# ProProject_Access_Control_USB_Hub_Switch.net
KiCad netlist of a schematic drawn in EasyEDA Pro
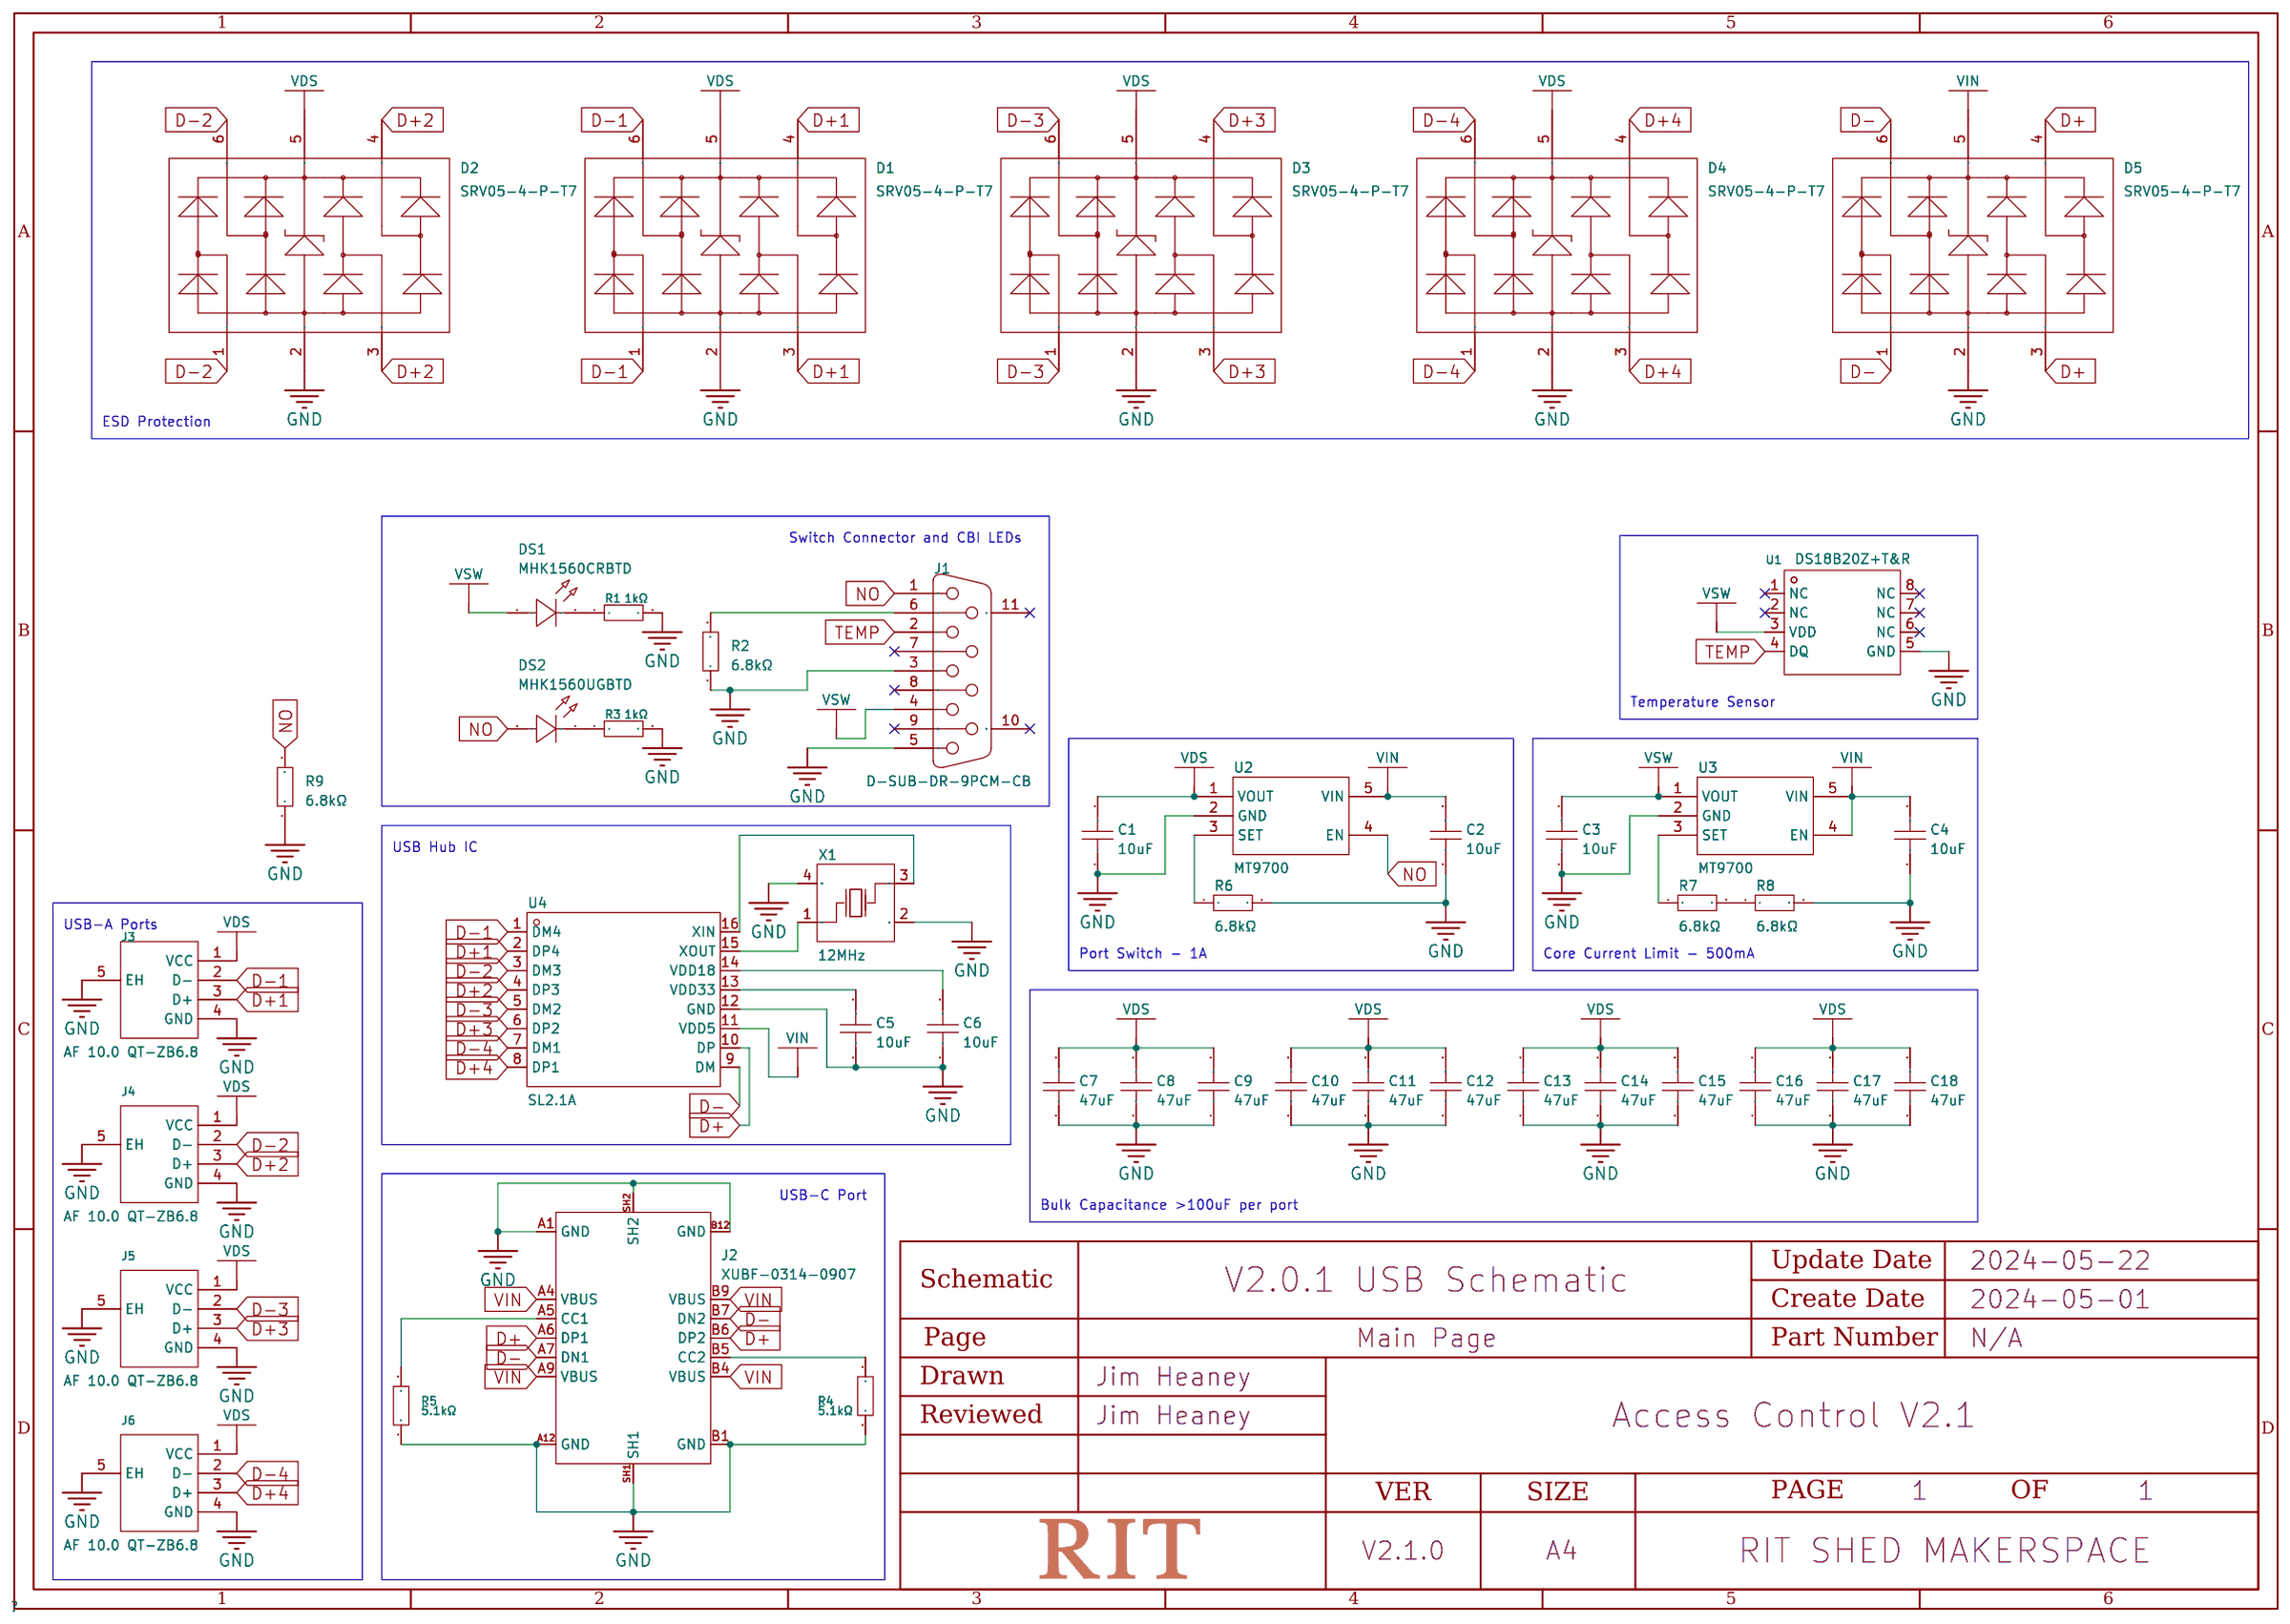
[diagram p0: schematic sheet]

(export (version "E")
  (design (tool "Eeschema 10.0.6"))
  (components
    (comp (ref "C1")
      (value "10uF")
      (footprint "easyedapro:C0603")
      (fields
        (field (name "Manufacturer Part") "CL10A106MA8NRNC")
        (field (name "Manufacturer") "SAMSUNG(三星)")
      )
      (libsource (lib "easyedapro") (part "CL10A106MA8NRNC"))
    )
    (comp (ref "C2")
      (value "10uF")
      (footprint "easyedapro:C0603")
      (fields
        (field (name "Manufacturer Part") "CL10A106MA8NRNC")
        (field (name "Manufacturer") "SAMSUNG(三星)")
      )
      (libsource (lib "easyedapro") (part "CL10A106MA8NRNC"))
    )
    (comp (ref "C3")
      (value "10uF")
      (footprint "easyedapro:C0603")
      (fields
        (field (name "Manufacturer Part") "CL10A106MA8NRNC")
        (field (name "Manufacturer") "SAMSUNG(三星)")
      )
      (libsource (lib "easyedapro") (part "CL10A106MA8NRNC"))
    )
    (comp (ref "C4")
      (value "10uF")
      (footprint "easyedapro:C0603")
      (fields
        (field (name "Manufacturer Part") "CL10A106MA8NRNC")
        (field (name "Manufacturer") "SAMSUNG(三星)")
      )
      (libsource (lib "easyedapro") (part "CL10A106MA8NRNC"))
    )
    (comp (ref "C5")
      (value "10uF")
      (footprint "easyedapro:C0603")
      (fields
        (field (name "Manufacturer Part") "CL10A106MA8NRNC")
        (field (name "Manufacturer") "SAMSUNG(三星)")
      )
      (libsource (lib "easyedapro") (part "CL10A106MA8NRNC"))
    )
    (comp (ref "C6")
      (value "10uF")
      (footprint "easyedapro:C0603")
      (fields
        (field (name "Manufacturer Part") "CL10A106MA8NRNC")
        (field (name "Manufacturer") "SAMSUNG(三星)")
      )
      (libsource (lib "easyedapro") (part "CL10A106MA8NRNC"))
    )
    (comp (ref "C7")
      (value "47uF")
      (footprint "easyedapro:C1206")
      (fields
        (field (name "Manufacturer Part") "CL31A476MPHNNNE")
        (field (name "Manufacturer") "SAMSUNG(三星)")
        (field (name "Tolerance") "±20%")
      )
      (libsource (lib "easyedapro") (part "CL31A476MPHNNNE"))
    )
    (comp (ref "C8")
      (value "47uF")
      (footprint "easyedapro:C1206")
      (fields
        (field (name "Manufacturer Part") "CL31A476MPHNNNE")
        (field (name "Manufacturer") "SAMSUNG(三星)")
        (field (name "Tolerance") "±20%")
      )
      (libsource (lib "easyedapro") (part "CL31A476MPHNNNE"))
    )
    (comp (ref "C9")
      (value "47uF")
      (footprint "easyedapro:C1206")
      (fields
        (field (name "Manufacturer Part") "CL31A476MPHNNNE")
        (field (name "Manufacturer") "SAMSUNG(三星)")
        (field (name "Tolerance") "±20%")
      )
      (libsource (lib "easyedapro") (part "CL31A476MPHNNNE"))
    )
    (comp (ref "C10")
      (value "47uF")
      (footprint "easyedapro:C1206")
      (fields
        (field (name "Manufacturer Part") "CL31A476MPHNNNE")
        (field (name "Manufacturer") "SAMSUNG(三星)")
        (field (name "Tolerance") "±20%")
      )
      (libsource (lib "easyedapro") (part "CL31A476MPHNNNE"))
    )
    (comp (ref "C11")
      (value "47uF")
      (footprint "easyedapro:C1206")
      (fields
        (field (name "Manufacturer Part") "CL31A476MPHNNNE")
        (field (name "Manufacturer") "SAMSUNG(三星)")
        (field (name "Tolerance") "±20%")
      )
      (libsource (lib "easyedapro") (part "CL31A476MPHNNNE"))
    )
    (comp (ref "C12")
      (value "47uF")
      (footprint "easyedapro:C1206")
      (fields
        (field (name "Manufacturer Part") "CL31A476MPHNNNE")
        (field (name "Manufacturer") "SAMSUNG(三星)")
        (field (name "Tolerance") "±20%")
      )
      (libsource (lib "easyedapro") (part "CL31A476MPHNNNE"))
    )
    (comp (ref "C13")
      (value "47uF")
      (footprint "easyedapro:C1206")
      (fields
        (field (name "Manufacturer Part") "CL31A476MPHNNNE")
        (field (name "Manufacturer") "SAMSUNG(三星)")
        (field (name "Tolerance") "±20%")
      )
      (libsource (lib "easyedapro") (part "CL31A476MPHNNNE"))
    )
    (comp (ref "C14")
      (value "47uF")
      (footprint "easyedapro:C1206")
      (fields
        (field (name "Manufacturer Part") "CL31A476MPHNNNE")
        (field (name "Manufacturer") "SAMSUNG(三星)")
        (field (name "Tolerance") "±20%")
      )
      (libsource (lib "easyedapro") (part "CL31A476MPHNNNE"))
    )
    (comp (ref "C15")
      (value "47uF")
      (footprint "easyedapro:C1206")
      (fields
        (field (name "Manufacturer Part") "CL31A476MPHNNNE")
        (field (name "Manufacturer") "SAMSUNG(三星)")
        (field (name "Tolerance") "±20%")
      )
      (libsource (lib "easyedapro") (part "CL31A476MPHNNNE"))
    )
    (comp (ref "C16")
      (value "47uF")
      (footprint "easyedapro:C1206")
      (fields
        (field (name "Manufacturer Part") "CL31A476MPHNNNE")
        (field (name "Manufacturer") "SAMSUNG(三星)")
        (field (name "Tolerance") "±20%")
      )
      (libsource (lib "easyedapro") (part "CL31A476MPHNNNE"))
    )
    (comp (ref "C17")
      (value "47uF")
      (footprint "easyedapro:C1206")
      (fields
        (field (name "Manufacturer Part") "CL31A476MPHNNNE")
        (field (name "Manufacturer") "SAMSUNG(三星)")
        (field (name "Tolerance") "±20%")
      )
      (libsource (lib "easyedapro") (part "CL31A476MPHNNNE"))
    )
    (comp (ref "C18")
      (value "47uF")
      (footprint "easyedapro:C1206")
      (fields
        (field (name "Manufacturer Part") "CL31A476MPHNNNE")
        (field (name "Manufacturer") "SAMSUNG(三星)")
        (field (name "Tolerance") "±20%")
      )
      (libsource (lib "easyedapro") (part "CL31A476MPHNNNE"))
    )
    (comp (ref "D1")
      (value "SRV05-4-P-T7")
      (footprint "easyedapro:SOT-23-6_L2.9-W1.6-P0.95-LS2.8-BR")
      (fields (field (name "Manufacturer") "PROTEK"))
      (libsource (lib "easyedapro") (part "SRV05-4-P-T7"))
    )
    (comp (ref "D2")
      (value "SRV05-4-P-T7")
      (footprint "easyedapro:SOT-23-6_L2.9-W1.6-P0.95-LS2.8-BR")
      (fields (field (name "Manufacturer") "PROTEK"))
      (libsource (lib "easyedapro") (part "SRV05-4-P-T7"))
    )
    (comp (ref "D3")
      (value "SRV05-4-P-T7")
      (footprint "easyedapro:SOT-23-6_L2.9-W1.6-P0.95-LS2.8-BR")
      (fields (field (name "Manufacturer") "PROTEK"))
      (libsource (lib "easyedapro") (part "SRV05-4-P-T7"))
    )
    (comp (ref "D4")
      (value "SRV05-4-P-T7")
      (footprint "easyedapro:SOT-23-6_L2.9-W1.6-P0.95-LS2.8-BR")
      (fields (field (name "Manufacturer") "PROTEK"))
      (libsource (lib "easyedapro") (part "SRV05-4-P-T7"))
    )
    (comp (ref "D5")
      (value "SRV05-4-P-T7")
      (footprint "easyedapro:SOT-23-6_L2.9-W1.6-P0.95-LS2.8-BR")
      (fields (field (name "Manufacturer") "PROTEK"))
      (libsource (lib "easyedapro") (part "SRV05-4-P-T7"))
    )
    (comp (ref "DS1")
      (value "MHK1560CRBTD")
      (footprint "easyedapro:LED-TH_MHK1560UGBTD")
      (fields (field (name "Manufacturer") "MEIHUA(美华)"))
      (libsource (lib "easyedapro") (part "MHK1560CGBTD"))
    )
    (comp (ref "DS2")
      (value "MHK1560UGBTD")
      (footprint "easyedapro:LED-TH_MHK1560UGBTD")
      (fields (field (name "Manufacturer") "MEIHUA(美华)"))
      (libsource (lib "easyedapro") (part "MHK1560UGBTD"))
    )
    (comp (ref "J1")
      (value "D-SUB-DR-9PCM-CB")
      (footprint "easyedapro:DB9-TH_ID09S33E4GV00LF")
      (fields (field (name "Manufacturer") "XUNPU(讯普)"))
      (libsource (lib "easyedapro") (part "D-SUB-DR-9PCM-CB"))
    )
    (comp (ref "J2")
      (value "XUBF-0314-0907")
      (footprint "easyedapro:TYPE-C-TH_TYPE-C-14P-CC-2.6")
      (description "DIY of C7527703")
      (fields (field (name "Manufacturer") "Lian Xin Technology"))
      (libsource (lib "easyedapro") (part "TYPE-C 14P CC-2.6"))
    )
    (comp (ref "J3")
      (value "AF 10.0 QT-ZB6.8")
      (footprint "easyedapro:USB-A-SMD_AF-10.0-QT-ZB6.8")
      (fields (field (name "Manufacturer") "SHOU HAN(首韩)"))
      (libsource (lib "easyedapro") (part "AF 10.0 QT-ZB6.8"))
    )
    (comp (ref "J4")
      (value "AF 10.0 QT-ZB6.8")
      (footprint "easyedapro:USB-A-SMD_AF-10.0-QT-ZB6.8")
      (fields (field (name "Manufacturer") "SHOU HAN(首韩)"))
      (libsource (lib "easyedapro") (part "AF 10.0 QT-ZB6.8"))
    )
    (comp (ref "J5")
      (value "AF 10.0 QT-ZB6.8")
      (footprint "easyedapro:USB-A-SMD_AF-10.0-QT-ZB6.8")
      (fields (field (name "Manufacturer") "SHOU HAN(首韩)"))
      (libsource (lib "easyedapro") (part "AF 10.0 QT-ZB6.8"))
    )
    (comp (ref "J6")
      (value "AF 10.0 QT-ZB6.8")
      (footprint "easyedapro:USB-A-SMD_AF-10.0-QT-ZB6.8")
      (fields (field (name "Manufacturer") "SHOU HAN(首韩)"))
      (libsource (lib "easyedapro") (part "AF 10.0 QT-ZB6.8"))
    )
    (comp (ref "R1")
      (value "1kΩ")
      (footprint "easyedapro:R0603")
      (fields
        (field (name "Manufacturer Part") "0603WAF1001T5E")
        (field (name "Manufacturer") "UNI-ROYAL(厚声)")
      )
      (libsource (lib "easyedapro") (part "0603WAF1001T5E"))
    )
    (comp (ref "R2")
      (value "6.8kΩ")
      (footprint "easyedapro:R0603")
      (fields
        (field (name "Manufacturer Part") "0603WAF6801T5E")
        (field (name "Manufacturer") "UNI-ROYAL(厚声)")
      )
      (libsource (lib "easyedapro") (part "0603WAF6801T5E"))
    )
    (comp (ref "R3")
      (value "1kΩ")
      (footprint "easyedapro:R0603")
      (fields
        (field (name "Manufacturer Part") "0603WAF1001T5E")
        (field (name "Manufacturer") "UNI-ROYAL(厚声)")
      )
      (libsource (lib "easyedapro") (part "0603WAF1001T5E"))
    )
    (comp (ref "R4")
      (value "5.1kΩ")
      (footprint "easyedapro:R0603")
      (fields
        (field (name "Manufacturer Part") "0603WAF5101T5E")
        (field (name "Manufacturer") "UNI-ROYAL(厚声)")
      )
      (libsource (lib "easyedapro") (part "0603WAF5101T5E"))
    )
    (comp (ref "R5")
      (value "5.1kΩ")
      (footprint "easyedapro:R0603")
      (fields
        (field (name "Manufacturer Part") "0603WAF5101T5E")
        (field (name "Manufacturer") "UNI-ROYAL(厚声)")
      )
      (libsource (lib "easyedapro") (part "0603WAF5101T5E"))
    )
    (comp (ref "R6")
      (value "6.8kΩ")
      (footprint "easyedapro:R0603")
      (fields
        (field (name "Manufacturer Part") "0603WAF6801T5E")
        (field (name "Manufacturer") "UNI-ROYAL(厚声)")
      )
      (libsource (lib "easyedapro") (part "0603WAF6801T5E"))
    )
    (comp (ref "R7")
      (value "6.8kΩ")
      (footprint "easyedapro:R0603")
      (fields
        (field (name "Manufacturer Part") "0603WAF6801T5E")
        (field (name "Manufacturer") "UNI-ROYAL(厚声)")
      )
      (libsource (lib "easyedapro") (part "0603WAF6801T5E"))
    )
    (comp (ref "R8")
      (value "6.8kΩ")
      (footprint "easyedapro:R0603")
      (fields
        (field (name "Manufacturer Part") "0603WAF6801T5E")
        (field (name "Manufacturer") "UNI-ROYAL(厚声)")
      )
      (libsource (lib "easyedapro") (part "0603WAF6801T5E"))
    )
    (comp (ref "R9")
      (value "6.8kΩ")
      (footprint "easyedapro:R0603")
      (fields
        (field (name "Manufacturer Part") "0603WAF6801T5E")
        (field (name "Manufacturer") "UNI-ROYAL(厚声)")
      )
      (libsource (lib "easyedapro") (part "0603WAF6801T5E"))
    )
    (comp (ref "U1")
      (value "DS18B20Z+T&R")
      (footprint "easyedapro:SOIC-8_L4.9-W3.9-P1.27-LS6.0-BL")
      (description "Supply Voltage:3V~5.5V Supply Voltage:3V~5.5V")
      (fields (field (name "Manufacturer") "ADI(亚德诺)/MAXIM(美信)"))
      (libsource (lib "easyedapro") (part "DS18B20Z+T&amp;R"))
    )
    (comp (ref "U2")
      (value "MT9700")
      (footprint "easyedapro:SOT-23-5_L3.0-W1.7-P0.95-LS2.8-BR")
      (fields (field (name "Manufacturer") "西安航天民芯"))
      (libsource (lib "easyedapro") (part "MT9700"))
    )
    (comp (ref "U3")
      (value "MT9700")
      (footprint "easyedapro:SOT-23-5_L3.0-W1.7-P0.95-LS2.8-BR")
      (fields (field (name "Manufacturer") "西安航天民芯"))
      (libsource (lib "easyedapro") (part "MT9700"))
    )
    (comp (ref "U4")
      (value "SL2.1A")
      (footprint "easyedapro:SOP-16_L10.0-W3.9-P1.27-LS6.0-BL")
      (fields (field (name "Manufacturer") "CoreChips(和芯润德)"))
      (libsource (lib "easyedapro") (part "SL2.1A"))
    )
    (comp (ref "X1")
      (value "12MHz")
      (footprint "easyedapro:OSC-SMD_4P-L3.2-W2.5-BL")
      (fields (field (name "Manufacturer Part") "X322512MSB4SI") (field (name "Manufacturer") "YXC(扬兴晶振)"))
      (libsource (lib "easyedapro") (part "X322512MSB4SI"))
    )
  )
  (nets
    (net (code "1") (name "D+") (class "Default")
      (node (ref "D5") (pin "3") (pinfunction "3_3") (pintype "input"))
      (node (ref "D5") (pin "4") (pinfunction "4_4") (pintype "input"))
      (node (ref "J2") (pin "A6") (pinfunction "DP1_A6") (pintype "input"))
      (node (ref "J2") (pin "B6") (pinfunction "DP2_B6") (pintype "input"))
      (node (ref "U4") (pin "10") (pinfunction "DP_10") (pintype "input"))
    )
    (net (code "2") (name "D+1") (class "Default")
      (node (ref "D1") (pin "3") (pinfunction "3_3") (pintype "input"))
      (node (ref "D1") (pin "4") (pinfunction "4_4") (pintype "input"))
      (node (ref "J3") (pin "3") (pinfunction "D+_3") (pintype "input"))
      (node (ref "U4") (pin "2") (pinfunction "DP4_2") (pintype "input"))
    )
    (net (code "3") (name "D+2") (class "Default")
      (node (ref "D2") (pin "3") (pinfunction "3_3") (pintype "input"))
      (node (ref "D2") (pin "4") (pinfunction "4_4") (pintype "input"))
      (node (ref "J4") (pin "3") (pinfunction "D+_3") (pintype "input"))
      (node (ref "U4") (pin "4") (pinfunction "DP3_4") (pintype "input"))
    )
    (net (code "4") (name "D+3") (class "Default")
      (node (ref "D3") (pin "3") (pinfunction "3_3") (pintype "input"))
      (node (ref "D3") (pin "4") (pinfunction "4_4") (pintype "input"))
      (node (ref "J5") (pin "3") (pinfunction "D+_3") (pintype "input"))
      (node (ref "U4") (pin "6") (pinfunction "DP2_6") (pintype "input"))
    )
    (net (code "5") (name "D+4") (class "Default")
      (node (ref "D4") (pin "3") (pinfunction "3_3") (pintype "input"))
      (node (ref "D4") (pin "4") (pinfunction "4_4") (pintype "input"))
      (node (ref "J6") (pin "3") (pinfunction "D+_3") (pintype "input"))
      (node (ref "U4") (pin "8") (pinfunction "DP1_8") (pintype "input"))
    )
    (net (code "6") (name "D-") (class "Default")
      (node (ref "D5") (pin "1") (pinfunction "1_1") (pintype "input"))
      (node (ref "D5") (pin "6") (pinfunction "6_6") (pintype "input"))
      (node (ref "J2") (pin "A7") (pinfunction "DN1_A7") (pintype "input"))
      (node (ref "J2") (pin "B7") (pinfunction "DN2_B7") (pintype "input"))
      (node (ref "U4") (pin "9") (pinfunction "DM_9") (pintype "input"))
    )
    (net (code "7") (name "D-1") (class "Default")
      (node (ref "D1") (pin "1") (pinfunction "1_1") (pintype "input"))
      (node (ref "D1") (pin "6") (pinfunction "6_6") (pintype "input"))
      (node (ref "J3") (pin "2") (pinfunction "D-_2") (pintype "input"))
      (node (ref "U4") (pin "1") (pinfunction "DM4_1") (pintype "input"))
    )
    (net (code "8") (name "D-2") (class "Default")
      (node (ref "D2") (pin "1") (pinfunction "1_1") (pintype "input"))
      (node (ref "D2") (pin "6") (pinfunction "6_6") (pintype "input"))
      (node (ref "J4") (pin "2") (pinfunction "D-_2") (pintype "input"))
      (node (ref "U4") (pin "3") (pinfunction "DM3_3") (pintype "input"))
    )
    (net (code "9") (name "D-3") (class "Default")
      (node (ref "D3") (pin "1") (pinfunction "1_1") (pintype "input"))
      (node (ref "D3") (pin "6") (pinfunction "6_6") (pintype "input"))
      (node (ref "J5") (pin "2") (pinfunction "D-_2") (pintype "input"))
      (node (ref "U4") (pin "5") (pinfunction "DM2_5") (pintype "input"))
    )
    (net (code "10") (name "D-4") (class "Default")
      (node (ref "D4") (pin "1") (pinfunction "1_1") (pintype "input"))
      (node (ref "D4") (pin "6") (pinfunction "6_6") (pintype "input"))
      (node (ref "J6") (pin "2") (pinfunction "D-_2") (pintype "input"))
      (node (ref "U4") (pin "7") (pinfunction "DM1_7") (pintype "input"))
    )
    (net (code "11") (name "GND") (class "Default")
      (node (ref "C1") (pin "1") (pinfunction "1_1") (pintype "input"))
      (node (ref "C10") (pin "1") (pinfunction "1_1") (pintype "input"))
      (node (ref "C11") (pin "1") (pinfunction "1_1") (pintype "input"))
      (node (ref "C12") (pin "1") (pinfunction "1_1") (pintype "input"))
      (node (ref "C13") (pin "1") (pinfunction "1_1") (pintype "input"))
      (node (ref "C14") (pin "1") (pinfunction "1_1") (pintype "input"))
      (node (ref "C15") (pin "1") (pinfunction "1_1") (pintype "input"))
      (node (ref "C16") (pin "1") (pinfunction "1_1") (pintype "input"))
      (node (ref "C17") (pin "1") (pinfunction "1_1") (pintype "input"))
      (node (ref "C18") (pin "1") (pinfunction "1_1") (pintype "input"))
      (node (ref "C2") (pin "1") (pinfunction "1_1") (pintype "input"))
      (node (ref "C3") (pin "1") (pinfunction "1_1") (pintype "input"))
      (node (ref "C4") (pin "1") (pinfunction "1_1") (pintype "input"))
      (node (ref "C5") (pin "1") (pinfunction "1_1") (pintype "input"))
      (node (ref "C6") (pin "1") (pinfunction "1_1") (pintype "input"))
      (node (ref "C7") (pin "1") (pinfunction "1_1") (pintype "input"))
      (node (ref "C8") (pin "1") (pinfunction "1_1") (pintype "input"))
      (node (ref "C9") (pin "1") (pinfunction "1_1") (pintype "input"))
      (node (ref "D1") (pin "2") (pinfunction "2_2") (pintype "input"))
      (node (ref "D2") (pin "2") (pinfunction "2_2") (pintype "input"))
      (node (ref "D3") (pin "2") (pinfunction "2_2") (pintype "input"))
      (node (ref "D4") (pin "2") (pinfunction "2_2") (pintype "input"))
      (node (ref "D5") (pin "2") (pinfunction "2_2") (pintype "input"))
      (node (ref "J1") (pin "3") (pinfunction "3_3") (pintype "input"))
      (node (ref "J1") (pin "5") (pinfunction "5_5") (pintype "input"))
      (node (ref "J2") (pin "A1") (pinfunction "GND_A1") (pintype "input"))
      (node (ref "J2") (pin "A12") (pinfunction "GND_A12") (pintype "input"))
      (node (ref "J2") (pin "B1") (pinfunction "GND_B1") (pintype "input"))
      (node (ref "J2") (pin "B12") (pinfunction "GND_B12") (pintype "input"))
      (node (ref "J2") (pin "SH1") (pinfunction "SH1_SH1") (pintype "input"))
      (node (ref "J2") (pin "SH2") (pinfunction "SH2_SH2") (pintype "input"))
      (node (ref "J3") (pin "4") (pinfunction "GND_4") (pintype "input"))
      (node (ref "J3") (pin "5") (pinfunction "EH_5") (pintype "input"))
      (node (ref "J4") (pin "4") (pinfunction "GND_4") (pintype "input"))
      (node (ref "J4") (pin "5") (pinfunction "EH_5") (pintype "input"))
      (node (ref "J5") (pin "4") (pinfunction "GND_4") (pintype "input"))
      (node (ref "J5") (pin "5") (pinfunction "EH_5") (pintype "input"))
      (node (ref "J6") (pin "4") (pinfunction "GND_4") (pintype "input"))
      (node (ref "J6") (pin "5") (pinfunction "EH_5") (pintype "input"))
      (node (ref "R1") (pin "2") (pinfunction "2_2") (pintype "input"))
      (node (ref "R2") (pin "1") (pinfunction "1_1") (pintype "input"))
      (node (ref "R3") (pin "2") (pinfunction "2_2") (pintype "input"))
      (node (ref "R4") (pin "1") (pinfunction "1_1") (pintype "input"))
      (node (ref "R5") (pin "1") (pinfunction "1_1") (pintype "input"))
      (node (ref "R6") (pin "2") (pinfunction "2_2") (pintype "input"))
      (node (ref "R8") (pin "2") (pinfunction "2_2") (pintype "input"))
      (node (ref "R9") (pin "1") (pinfunction "1_1") (pintype "input"))
      (node (ref "U1") (pin "5") (pinfunction "GND_5") (pintype "input"))
      (node (ref "U2") (pin "2") (pinfunction "GND_2") (pintype "input"))
      (node (ref "U3") (pin "2") (pinfunction "GND_2") (pintype "input"))
      (node (ref "U4") (pin "12") (pinfunction "GND_12") (pintype "input"))
      (node (ref "X1") (pin "2") (pinfunction "GND_2") (pintype "input"))
      (node (ref "X1") (pin "4") (pinfunction "GND_4") (pintype "input"))
    )
    (net (code "12") (name "NO") (class "Default")
      (node (ref "DS2") (pin "2") (pinfunction "A_2") (pintype "unspecified"))
      (node (ref "J1") (pin "1") (pinfunction "1_1") (pintype "input"))
      (node (ref "R9") (pin "2") (pinfunction "2_2") (pintype "input"))
      (node (ref "U2") (pin "4") (pinfunction "EN_4") (pintype "input"))
    )
    (net (code "13") (name "Net-(DS1-K)") (class "Default")
      (node (ref "DS1") (pin "1") (pinfunction "K_1") (pintype "unspecified"))
      (node (ref "R1") (pin "1") (pinfunction "1_1") (pintype "input"))
    )
    (net (code "14") (name "Net-(DS2-K)") (class "Default")
      (node (ref "DS2") (pin "1") (pinfunction "K_1") (pintype "unspecified"))
      (node (ref "R3") (pin "1") (pinfunction "1_1") (pintype "input"))
    )
    (net (code "15") (name "Net-(J1-Pad6)") (class "Default")
      (node (ref "J1") (pin "6") (pinfunction "6_6") (pintype "input"))
      (node (ref "R2") (pin "2") (pinfunction "2_2") (pintype "input"))
    )
    (net (code "16") (name "Net-(J2-CC1)") (class "Default")
      (node (ref "J2") (pin "A5") (pinfunction "CC1_A5") (pintype "input"))
      (node (ref "R5") (pin "2") (pinfunction "2_2") (pintype "input"))
    )
    (net (code "17") (name "Net-(J2-CC2)") (class "Default")
      (node (ref "J2") (pin "B5") (pinfunction "CC2_B5") (pintype "input"))
      (node (ref "R4") (pin "2") (pinfunction "2_2") (pintype "input"))
    )
    (net (code "18") (name "Net-(R7-Pad2)") (class "Default")
      (node (ref "R7") (pin "2") (pinfunction "2_2") (pintype "input"))
      (node (ref "R8") (pin "1") (pinfunction "1_1") (pintype "input"))
    )
    (net (code "19") (name "Net-(U2-SET)") (class "Default")
      (node (ref "R6") (pin "1") (pinfunction "1_1") (pintype "input"))
      (node (ref "U2") (pin "3") (pinfunction "SET_3") (pintype "input"))
    )
    (net (code "20") (name "Net-(U3-SET)") (class "Default")
      (node (ref "R7") (pin "1") (pinfunction "1_1") (pintype "input"))
      (node (ref "U3") (pin "3") (pinfunction "SET_3") (pintype "input"))
    )
    (net (code "21") (name "Net-(U4-VDD18)") (class "Default")
      (node (ref "C6") (pin "2") (pinfunction "2_2") (pintype "input"))
      (node (ref "U4") (pin "14") (pinfunction "VDD18_14") (pintype "input"))
    )
    (net (code "22") (name "Net-(U4-VDD33)") (class "Default")
      (node (ref "C5") (pin "2") (pinfunction "2_2") (pintype "input"))
      (node (ref "U4") (pin "13") (pinfunction "VDD33_13") (pintype "input"))
    )
    (net (code "23") (name "Net-(U4-XIN)") (class "Default")
      (node (ref "U4") (pin "16") (pinfunction "XIN_16") (pintype "input"))
      (node (ref "X1") (pin "3") (pinfunction "OSC2_3") (pintype "input"))
    )
    (net (code "24") (name "Net-(U4-XOUT)") (class "Default")
      (node (ref "U4") (pin "15") (pinfunction "XOUT_15") (pintype "input"))
      (node (ref "X1") (pin "1") (pinfunction "OSC1_1") (pintype "input"))
    )
    (net (code "25") (name "TEMP") (class "Default")
      (node (ref "J1") (pin "2") (pinfunction "2_2") (pintype "input"))
      (node (ref "U1") (pin "4") (pinfunction "DQ_4") (pintype "input"))
    )
    (net (code "26") (name "VDS") (class "Default")
      (node (ref "C1") (pin "2") (pinfunction "2_2") (pintype "input"))
      (node (ref "C10") (pin "2") (pinfunction "2_2") (pintype "input"))
      (node (ref "C11") (pin "2") (pinfunction "2_2") (pintype "input"))
      (node (ref "C12") (pin "2") (pinfunction "2_2") (pintype "input"))
      (node (ref "C13") (pin "2") (pinfunction "2_2") (pintype "input"))
      (node (ref "C14") (pin "2") (pinfunction "2_2") (pintype "input"))
      (node (ref "C15") (pin "2") (pinfunction "2_2") (pintype "input"))
      (node (ref "C16") (pin "2") (pinfunction "2_2") (pintype "input"))
      (node (ref "C17") (pin "2") (pinfunction "2_2") (pintype "input"))
      (node (ref "C18") (pin "2") (pinfunction "2_2") (pintype "input"))
      (node (ref "C7") (pin "2") (pinfunction "2_2") (pintype "input"))
      (node (ref "C8") (pin "2") (pinfunction "2_2") (pintype "input"))
      (node (ref "C9") (pin "2") (pinfunction "2_2") (pintype "input"))
      (node (ref "D1") (pin "5") (pinfunction "5_5") (pintype "input"))
      (node (ref "D2") (pin "5") (pinfunction "5_5") (pintype "input"))
      (node (ref "D3") (pin "5") (pinfunction "5_5") (pintype "input"))
      (node (ref "D4") (pin "5") (pinfunction "5_5") (pintype "input"))
      (node (ref "J3") (pin "1") (pinfunction "VCC_1") (pintype "input"))
      (node (ref "J4") (pin "1") (pinfunction "VCC_1") (pintype "input"))
      (node (ref "J5") (pin "1") (pinfunction "VCC_1") (pintype "input"))
      (node (ref "J6") (pin "1") (pinfunction "VCC_1") (pintype "input"))
      (node (ref "U2") (pin "1") (pinfunction "VOUT_1") (pintype "input"))
    )
    (net (code "27") (name "VIN") (class "Default")
      (node (ref "C2") (pin "2") (pinfunction "2_2") (pintype "input"))
      (node (ref "C4") (pin "2") (pinfunction "2_2") (pintype "input"))
      (node (ref "D5") (pin "5") (pinfunction "5_5") (pintype "input"))
      (node (ref "J2") (pin "A4") (pinfunction "VBUS_A4") (pintype "input"))
      (node (ref "J2") (pin "A9") (pinfunction "VBUS_A9") (pintype "input"))
      (node (ref "J2") (pin "B4") (pinfunction "VBUS_B4") (pintype "input"))
      (node (ref "J2") (pin "B9") (pinfunction "VBUS_B9") (pintype "input"))
      (node (ref "U2") (pin "5") (pinfunction "VIN_5") (pintype "input"))
      (node (ref "U3") (pin "4") (pinfunction "EN_4") (pintype "input"))
      (node (ref "U3") (pin "5") (pinfunction "VIN_5") (pintype "input"))
      (node (ref "U4") (pin "11") (pinfunction "VDD5_11") (pintype "input"))
    )
    (net (code "28") (name "VSW") (class "Default")
      (node (ref "C3") (pin "2") (pinfunction "2_2") (pintype "input"))
      (node (ref "DS1") (pin "2") (pinfunction "A_2") (pintype "unspecified"))
      (node (ref "J1") (pin "4") (pinfunction "4_4") (pintype "input"))
      (node (ref "U1") (pin "3") (pinfunction "VDD_3") (pintype "input"))
      (node (ref "U3") (pin "1") (pinfunction "VOUT_1") (pintype "input"))
    )
    (net (code "29") (name "unconnected-(J1-MH1-Pad10)") (class "Default")
      (node (ref "J1") (pin "10") (pinfunction "MH1_10") (pintype "input+no_connect"))
    )
    (net (code "30") (name "unconnected-(J1-MH2-Pad11)") (class "Default")
      (node (ref "J1") (pin "11") (pinfunction "MH2_11") (pintype "input+no_connect"))
    )
    (net (code "31") (name "unconnected-(J1-Pad7)") (class "Default")
      (node (ref "J1") (pin "7") (pinfunction "7_7") (pintype "input+no_connect"))
    )
    (net (code "32") (name "unconnected-(J1-Pad8)") (class "Default")
      (node (ref "J1") (pin "8") (pinfunction "8_8") (pintype "input+no_connect"))
    )
    (net (code "33") (name "unconnected-(J1-Pad9)") (class "Default")
      (node (ref "J1") (pin "9") (pinfunction "9_9") (pintype "input+no_connect"))
    )
    (net (code "34") (name "unconnected-(U1-NC-Pad1)") (class "Default")
      (node (ref "U1") (pin "1") (pinfunction "NC_1") (pintype "input+no_connect"))
    )
    (net (code "35") (name "unconnected-(U1-NC-Pad2)") (class "Default")
      (node (ref "U1") (pin "2") (pinfunction "NC_2") (pintype "input+no_connect"))
    )
    (net (code "36") (name "unconnected-(U1-NC-Pad6)") (class "Default")
      (node (ref "U1") (pin "6") (pinfunction "NC_6") (pintype "input+no_connect"))
    )
    (net (code "37") (name "unconnected-(U1-NC-Pad7)") (class "Default")
      (node (ref "U1") (pin "7") (pinfunction "NC_7") (pintype "input+no_connect"))
    )
    (net (code "38") (name "unconnected-(U1-NC-Pad8)") (class "Default")
      (node (ref "U1") (pin "8") (pinfunction "NC_8") (pintype "input+no_connect"))
    )
  )
)
